# DataDriven_sheet4_sim_connectors.net
KiCad netlist of a schematic drawn in Altium Designer
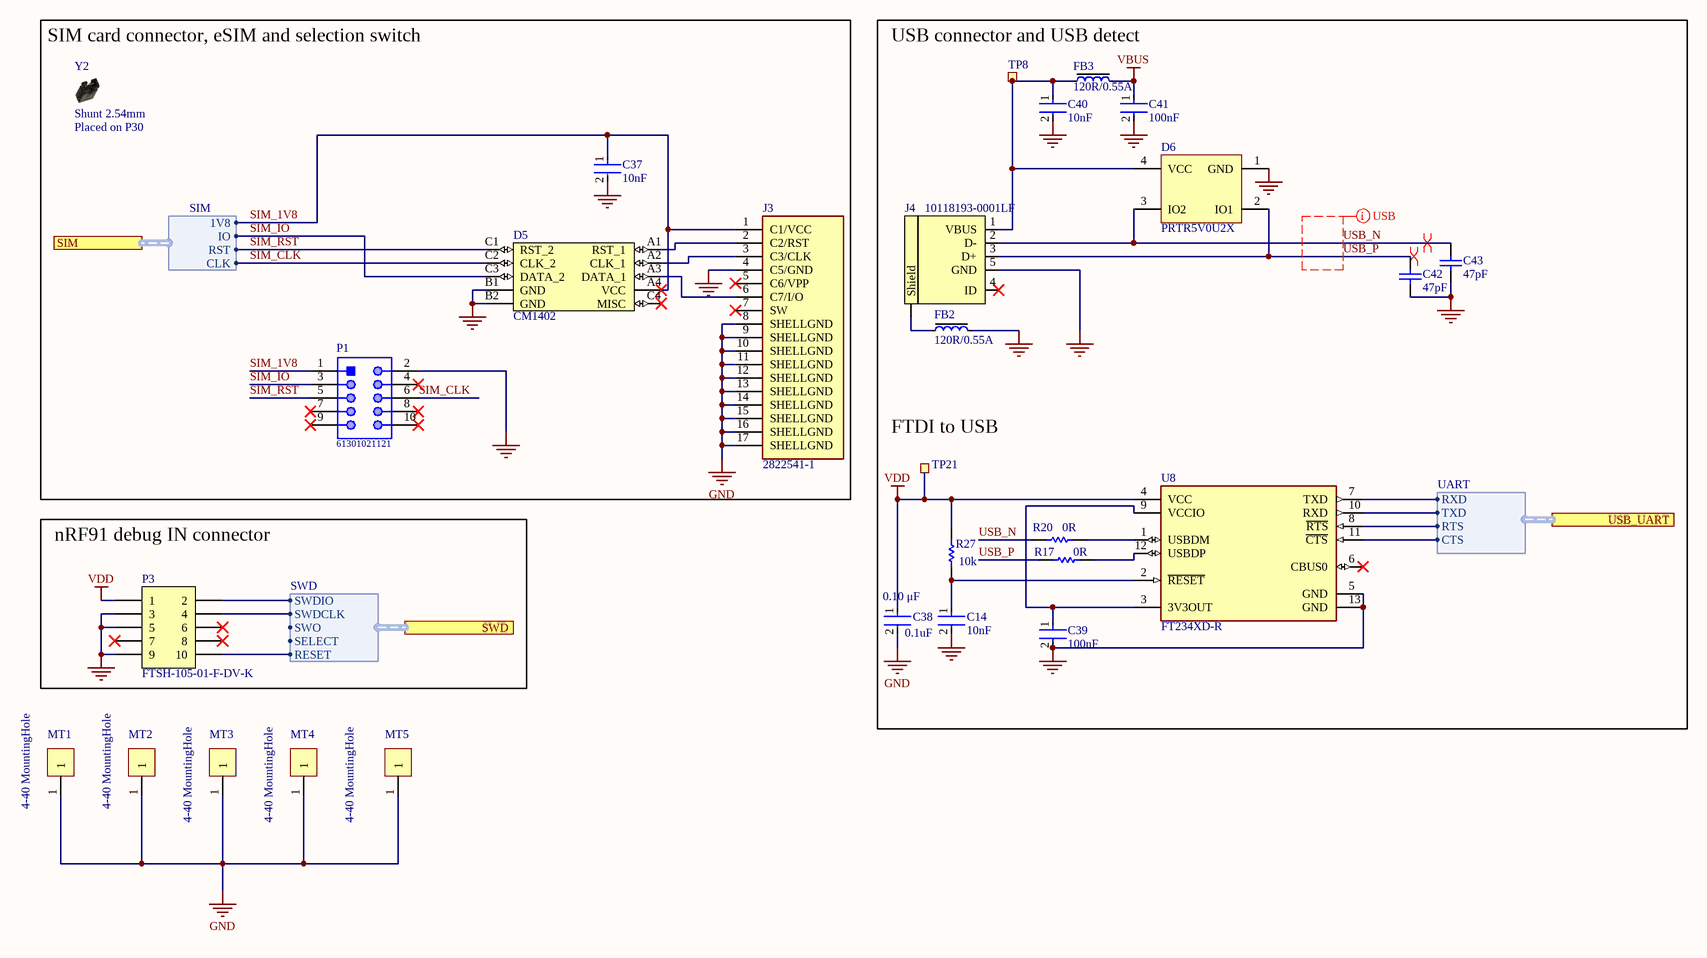
[diagram p0: DataDriven_sheet4_sim_connectors.SchDoc]

(export (version "E")
  (design (tool "Eeschema 10.0.6"))
  (components
    (comp (ref "C14")
      (value "10nF")
      (footprint "FP-CC0603-DA-MFG")
      (description "CAP CER 10000PF 50V X7R 0603")
      (fields (field (name "TOLERANCE") "0.1") (field (name "MANUFACTURER PART NUMBER") "CC0603KRX7R9BB103"))
      (libsource (lib "Altium Content Vault") (part "11868f565c42a9108669ba33697ecf6"))
    )
    (comp (ref "C37")
      (value "10nF")
      (footprint "FP-CC0603-DA-MFG")
      (description "CAP CER 10000PF 50V X7R 0603")
      (fields (field (name "TOLERANCE") "0.1") (field (name "MANUFACTURER PART NUMBER") "CC0603KRX7R9BB103"))
      (libsource (lib "Altium Content Vault") (part "11868f565c42a9108669ba33697ecf6"))
    )
    (comp (ref "C38")
      (value "0.1uF")
      (footprint "FP-C0603C-CF-MFG")
      (description "CAP CER 0.1UF 50V X7R 0603")
      (fields
        (field (name "TOLERANCE") "0.1")
        (field (name "MANUFACTURER") "KEMET")
        (field (name "CAPACITANCE") "0.10 μF")
      )
      (libsource (lib "Altium Content Vault") (part "b4654b650e69147ec39a6b967a45e02"))
    )
    (comp (ref "C39")
      (value "100nF")
      (footprint "FP-CGA3E-0_3-0_1-IPC_A")
      (description "Cap Ceramic 100nF 50V X7R 10% Pad SMD 0603 +125°C Automotive T/R")
      (fields (field (name "TOLERANCE") "10%") (field (name "VOLTAGE") "50V"))
      (libsource (lib "Altium Content Vault") (part "b4654b650e69147ec39a6b967a45e02"))
    )
    (comp (ref "C40")
      (value "10nF")
      (footprint "FP-CC0603-DA-MFG")
      (description "CAP CER 10000PF 50V X7R 0603")
      (fields (field (name "TOLERANCE") "0.1") (field (name "MANUFACTURER PART NUMBER") "CC0603KRX7R9BB103"))
      (libsource (lib "Altium Content Vault") (part "11868f565c42a9108669ba33697ecf6"))
    )
    (comp (ref "C41")
      (value "100nF")
      (footprint "FP-CGA3E-0_3-0_1-MFG")
      (description "Cap Ceramic 100nF 50V X7R 10% Pad SMD 0603 +125°C Automotive T/R")
      (fields (field (name "TOLERANCE") "10%") (field (name "VOLTAGE") "50V"))
      (libsource (lib "Altium Content Vault") (part "b4654b650e69147ec39a6b967a45e02"))
    )
    (comp (ref "C42")
      (value "47pF")
      (footprint "CAPC1608X90X35ML10T15")
      (description "47 pF ±5% 50V Ceramic Capacitor C0G, NP0 0603 (1608 Metric)")
      (fields (field (name "MANUFACTURER") "Murata") (field (name "PART NUMBER") "GRM1885C1H470JA01D"))
      (libsource (lib "Altium Content Vault") (part "CAP"))
    )
    (comp (ref "C43")
      (value "47pF")
      (footprint "CAPC1608X90X35ML10T15")
      (description "47 pF ±5% 50V Ceramic Capacitor C0G, NP0 0603 (1608 Metric)")
      (fields (field (name "MANUFACTURER") "Murata") (field (name "PART NUMBER") "GRM1885C1H470JA01D"))
      (libsource (lib "Altium Content Vault") (part "CAP"))
    )
    (comp (ref "D5")
      (value "CM1402")
      (footprint "pca10090:CM1402")
      (description "EMI Network Filter Arrays SIM CARD EMI FILTER WITH ESD PROTECTION")
      (fields
        (field (name "MANUFACTURER") "ON Semiconductor")
        (field (name "MANUFACTURER PART NUMBER") "CM1402-03CP")
        (field (name "AUTHOR") "rsk")
      )
      (libsource (lib "AltiumLib") (part "CM1402"))
    )
    (comp (ref "D6")
      (value "PRTR5V0U2X")
      (footprint "pca10090:SOT190P230X110-4L")
      (description "Ultra low capacitance double rail-to-rail ESD protection diode")
      (fields (field (name "MANUFACTURER") "NXP Semiconductors") (field (name "AUTHOR") "rsk"))
      (libsource (lib "AltiumLib") (part "PRTR5V0U2X"))
    )
    (comp (ref "FB2")
      (value "120R/0.55A")
      (footprint "pca10090:INDC1005X04L")
      (description "Ferrite Bead, 120 Ohm @ 100MHz, 500mA, 250 mOhm Max")
      (fields
        (field (name "PART NUMBER") "FB0402-120R@100M-500mA")
        (field (name "MANUFACTURER") "Murata")
        (field (name "AUTHOR") "rsk")
      )
      (libsource (lib "AltiumLib") (part "IND_F"))
    )
    (comp (ref "FB3")
      (value "120R/0.55A")
      (footprint "pca10090:INDC1005X04L")
      (description "Ferrite Bead, 120 Ohm @ 100MHz, 500mA, 250 mOhm Max")
      (fields
        (field (name "PART NUMBER") "FB0402-120R@100M-500mA")
        (field (name "MANUFACTURER") "Murata")
        (field (name "AUTHOR") "rsk")
      )
      (libsource (lib "AltiumLib") (part "IND_F"))
    )
    (comp (ref "J3")
      (value "2822541-1")
      (footprint "TE_2822541-1")
      (description "7 _6 + 1_ Position Card Connector Micro SIM Surface Mount, Right Angle Gold")
      (fields (field (name "MF") "TE Connectivity") (field (name "DIGI-KEY_PART_NUMBER") "A141365CT-ND"))
      (libsource (lib "DataDriven") (part "2822541-1"))
    )
    (comp (ref "J4")
      (value "10118193-0001LF")
      (footprint "pca10090:USB-Micro-B-RA-SMD-PiP")
      (description "USB - micro B USB 2.0 Receptacle Connector 5 Position Surface Mount, Right Angle; Through Hole")
      (fields (field (name "MANUFACTURER") "Amphenol ICC (FCI)") (field (name "AUTHOR") "rsk"))
      (libsource (lib "AltiumLib") (part "MiniUSB-AB-SMT"))
    )
    (comp (ref "MT1")
      (value "4-40 MountingHole")
      (footprint "4-40 Mounting Hole")
      (description "4-40 Mounting Hole")
      (libsource (lib "DataDriven") (part "4-40 MountingHole"))
    )
    (comp (ref "MT2")
      (value "4-40 MountingHole")
      (footprint "4-40 Mounting Hole")
      (description "4-40 Mounting Hole")
      (libsource (lib "DataDriven") (part "4-40 MountingHole"))
    )
    (comp (ref "MT3")
      (value "4-40 MountingHole")
      (footprint "4-40 Mounting Hole")
      (description "4-40 Mounting Hole")
      (libsource (lib "DataDriven") (part "4-40 MountingHole"))
    )
    (comp (ref "MT4")
      (value "4-40 MountingHole")
      (footprint "4-40 Mounting Hole")
      (description "4-40 Mounting Hole")
      (libsource (lib "DataDriven") (part "4-40 MountingHole"))
    )
    (comp (ref "MT5")
      (value "4-40 MountingHole")
      (footprint "4-40 Mounting Hole")
      (description "4-40 Mounting Hole")
      (libsource (lib "DataDriven") (part "4-40 MountingHole"))
    )
    (comp (ref "P1")
      (value "61301021121")
      (footprint "61301021121")
      (description "THT Vertical Pin Header WR-PHD, Pitch 2.54 mm, Dual Row, 10 pins")
      (fields (field (name "MANUFACTURER") "Wurth Elektronik") (field (name "PUBLISHER") "WurthElektronik"))
      (libsource (lib "Altium Content Vault") (part "WE-CN-2P-M-R10"))
    )
    (comp (ref "P3")
      (value "FTSH-105-01-F-DV-K")
      (footprint "pca10090:HDR_2x5-SMD-1.27mm-K")
      (description "Pin Header 2x5, 1.27mm (50mil), SMD, Keying Shroud")
      (fields
        (field (name "PART NUMBER") "Pin Header 2x5 SMD, 1.27mm, KS")
        (field (name "MANUFACTURER") "Samtec")
        (field (name "AUTHOR") "rsk")
      )
      (libsource (lib "AltiumLib") (part "CONN-2x5"))
    )
    (comp (ref "R17")
      (value "0R")
      (footprint "RESC1608X55X25ML10T15")
      (description "Chip Resistor, 0 Ohm, +/- 5%, 0.1 W, -55 to 155 degC, 0603 (1608 Metric), RoHS, Tape and Reel")
      (fields (field (name "TOLERANCE") "5%") (field (name "MANUFACTURER") "Yageo"))
      (libsource (lib "Altium Content Vault") (part "RES-2"))
    )
    (comp (ref "R20")
      (value "0R")
      (footprint "RESC1608X55X25ML10T15")
      (description "Chip Resistor, 0 Ohm, +/- 5%, 0.1 W, -55 to 155 degC, 0603 (1608 Metric), RoHS, Tape and Reel")
      (fields (field (name "TOLERANCE") "5%") (field (name "MANUFACTURER") "Yageo"))
      (libsource (lib "Altium Content Vault") (part "RES-2"))
    )
    (comp (ref "R27")
      (value "10k")
      (footprint "RESC1609X55X30LL15T15")
      (description "Chip Resistor, 10 KOhm, +/- 1%, 0.1 W, -55 to 155 degC, 0603 (1608 Metric), RoHS, Tape and Reel")
      (fields (field (name "TOLERANCE") "1%") (field (name "MANUFACTURER") "Panasonic"))
      (libsource (lib "Altium Content Vault") (part "RES-2"))
    )
    (comp (ref "TP8")
      (value "Ø1.5mm,SMD")
      (footprint "pca10090:TP_SMD_D1.5mm")
      (description "1.5mm circular SMD testpad")
      (fields
        (field (name "PART NUMBER") "TP_SMD_Ø1.5MM")
        (field (name "MANUFACTURER") "Nordic Semiconductor")
        (field (name "AUTHOR") "rsk")
      )
      (libsource (lib "AltiumLib") (part "TESTPAD"))
    )
    (comp (ref "TP21")
      (value "Ø1.5mm,SMD")
      (footprint "pca10090:TP_SMD_D1.5mm")
      (description "1.5mm circular SMD testpad")
      (fields
        (field (name "PART NUMBER") "TP_SMD_Ø1.5MM")
        (field (name "MANUFACTURER") "Nordic Semiconductor")
        (field (name "AUTHOR") "rsk")
      )
      (libsource (lib "AltiumLib") (part "TESTPAD"))
    )
    (comp (ref "U8")
      (value "FT234XD-R")
      (footprint "FP-DFN-12-MFG")
      (description "IC USB SERIAL BASIC UART 12DFN")
      (fields (field (name "MANUFACTURER") "FTDI"))
      (libsource (lib "Altium Content Vault") (part "4bef3367ed9f9051bcb84ab46edda1c"))
    )
    (comp (ref "Y2")
      (value "Shunt 2.54mm")
      (footprint "pca10090:Shunt_2.54mm_Horizontal")
      (description "Shunt Jumper 2.54mm Black")
      (fields
        (field (name "PART NUMBER") "SNT-100-RD-G")
        (field (name "ASSEMBLY") "Placed on P30")
        (field (name "MANUFACTURER") "Samtec")
        (field (name "AUTHOR") "rsk")
      )
      (libsource (lib "AltiumLib") (part "Shunt_Jumper_2.54"))
    )
  )
  (nets
    (net (code "4") (name "/CTS") (class "Default")
      (node (ref "U8") (pin "11") (pinfunction "~{CTS}_11") (pintype "input"))
    )
    (net (code "5") (name "/RESET") (class "Default")
      (node (ref "P3") (pin "10") (pinfunction "10_10") (pintype "passive"))
    )
    (net (code "6") (name "/RTS") (class "Default")
      (node (ref "U8") (pin "8") (pinfunction "~{RTS}_8") (pintype "input"))
    )
    (net (code "7") (name "/RXD") (class "Default")
      (node (ref "U8") (pin "7") (pinfunction "TXD_7") (pintype "output"))
    )
    (net (code "8") (name "/SIM_1V8") (class "Default")
      (node (ref "C37") (pin "1") (pinfunction "1_1") (pintype "passive"))
      (node (ref "D5") (pin "A4") (pinfunction "VCC_A4") (pintype "power_in"))
      (node (ref "J3") (pin "1") (pinfunction "C1/VCC_1") (pintype "passive"))
      (node (ref "P1") (pin "1") (pinfunction "1_1") (pintype "passive"))
    )
    (net (code "9") (name "/SIM_CLK") (class "Default")
      (node (ref "D5") (pin "C2") (pinfunction "CLK_2_C2") (pintype "bidirectional"))
      (node (ref "P1") (pin "6") (pinfunction "6_6") (pintype "passive"))
    )
    (net (code "10") (name "/SIM_IO") (class "Default")
      (node (ref "D5") (pin "C3") (pinfunction "DATA_2_C3") (pintype "bidirectional"))
      (node (ref "P1") (pin "3") (pinfunction "3_3") (pintype "passive"))
    )
    (net (code "11") (name "/SIM_RST") (class "Default")
      (node (ref "D5") (pin "C1") (pinfunction "RST_2_C1") (pintype "bidirectional"))
      (node (ref "P1") (pin "5") (pinfunction "5_5") (pintype "passive"))
    )
    (net (code "12") (name "/SWDCLK") (class "Default")
      (node (ref "P3") (pin "4") (pinfunction "4_4") (pintype "passive"))
    )
    (net (code "13") (name "/SWDIO") (class "Default")
      (node (ref "P3") (pin "2") (pinfunction "2_2") (pintype "passive"))
    )
    (net (code "14") (name "/TXD") (class "Default")
      (node (ref "U8") (pin "10") (pinfunction "RXD_10") (pintype "output"))
    )
    (net (code "15") (name "/USB_N") (class "Default")
      (node (ref "C43") (pin "2") (pinfunction "2_2") (pintype "passive"))
      (node (ref "D6") (pin "3") (pinfunction "IO2_3") (pintype "passive"))
      (node (ref "J4") (pin "2") (pinfunction "D-_2") (pintype "passive"))
      (node (ref "R20") (pin "1") (pinfunction "1_1") (pintype "passive"))
    )
    (net (code "16") (name "/USB_P") (class "Default")
      (node (ref "C42") (pin "2") (pinfunction "2_2") (pintype "passive"))
      (node (ref "D6") (pin "2") (pinfunction "IO1_2") (pintype "passive"))
      (node (ref "J4") (pin "3") (pinfunction "D+_3") (pintype "passive"))
      (node (ref "R17") (pin "1") (pinfunction "1_1") (pintype "passive"))
    )
    (net (code "20") (name "GND") (class "Default")
      (node (ref "C14") (pin "2") (pinfunction "2_2") (pintype "passive"))
      (node (ref "C37") (pin "2") (pinfunction "2_2") (pintype "passive"))
      (node (ref "C38") (pin "2") (pinfunction "2_2") (pintype "passive"))
      (node (ref "C39") (pin "2") (pinfunction "2_2") (pintype "passive"))
      (node (ref "C40") (pin "2") (pinfunction "2_2") (pintype "passive"))
      (node (ref "C41") (pin "2") (pinfunction "2_2") (pintype "passive"))
      (node (ref "C42") (pin "1") (pinfunction "1_1") (pintype "passive"))
      (node (ref "C43") (pin "1") (pinfunction "1_1") (pintype "passive"))
      (node (ref "D5") (pin "B1") (pinfunction "GND_B1") (pintype "power_in"))
      (node (ref "D5") (pin "B2") (pinfunction "GND_B2") (pintype "power_in"))
      (node (ref "D6") (pin "1") (pinfunction "GND_1") (pintype "passive"))
      (node (ref "FB2") (pin "2") (pinfunction "2_2") (pintype "passive"))
      (node (ref "J3") (pin "10") (pinfunction "SHELLGND_10") (pintype "passive"))
      (node (ref "J3") (pin "11") (pinfunction "SHELLGND_11") (pintype "passive"))
      (node (ref "J3") (pin "12") (pinfunction "SHELLGND_12") (pintype "passive"))
      (node (ref "J3") (pin "13") (pinfunction "SHELLGND_13") (pintype "passive"))
      (node (ref "J3") (pin "14") (pinfunction "SHELLGND_14") (pintype "passive"))
      (node (ref "J3") (pin "15") (pinfunction "SHELLGND_15") (pintype "passive"))
      (node (ref "J3") (pin "16") (pinfunction "SHELLGND_16") (pintype "passive"))
      (node (ref "J3") (pin "17") (pinfunction "SHELLGND_17") (pintype "passive"))
      (node (ref "J3") (pin "4") (pinfunction "C5/GND_4") (pintype "passive"))
      (node (ref "J3") (pin "8") (pinfunction "SHELLGND_8") (pintype "passive"))
      (node (ref "J3") (pin "9") (pinfunction "SHELLGND_9") (pintype "passive"))
      (node (ref "J4") (pin "5") (pinfunction "GND_5") (pintype "power_in"))
      (node (ref "MT1") (pin "1") (pinfunction "1_1") (pintype "passive"))
      (node (ref "MT2") (pin "1") (pinfunction "1_1") (pintype "passive"))
      (node (ref "MT3") (pin "1") (pinfunction "1_1") (pintype "passive"))
      (node (ref "MT4") (pin "1") (pinfunction "1_1") (pintype "passive"))
      (node (ref "MT5") (pin "1") (pinfunction "1_1") (pintype "passive"))
      (node (ref "P1") (pin "2") (pinfunction "2_2") (pintype "passive"))
      (node (ref "P3") (pin "3") (pinfunction "3_3") (pintype "passive"))
      (node (ref "P3") (pin "5") (pinfunction "5_5") (pintype "passive"))
      (node (ref "P3") (pin "9") (pinfunction "9_9") (pintype "passive"))
      (node (ref "U8") (pin "13") (pinfunction "GND_13") (pintype "power_in"))
      (node (ref "U8") (pin "5") (pinfunction "GND_5") (pintype "power_in"))
    )
    (net (code "21") (name "Net-(D5-CLK_1)") (class "Default")
      (node (ref "D5") (pin "A2") (pinfunction "CLK_1_A2") (pintype "bidirectional"))
      (node (ref "J3") (pin "3") (pinfunction "C3/CLK_3") (pintype "passive"))
    )
    (net (code "22") (name "Net-(D5-DATA_1)") (class "Default")
      (node (ref "D5") (pin "A3") (pinfunction "DATA_1_A3") (pintype "bidirectional"))
      (node (ref "J3") (pin "6") (pinfunction "C7/I/O_6") (pintype "passive"))
    )
    (net (code "23") (name "Net-(D5-RST_1)") (class "Default")
      (node (ref "D5") (pin "A1") (pinfunction "RST_1_A1") (pintype "bidirectional"))
      (node (ref "J3") (pin "2") (pinfunction "C2/RST_2") (pintype "passive"))
    )
    (net (code "24") (name "Net-(D6-VCC)") (class "Default")
      (node (ref "C40") (pin "1") (pinfunction "1_1") (pintype "passive"))
      (node (ref "D6") (pin "4") (pinfunction "VCC_4") (pintype "passive"))
      (node (ref "FB3") (pin "1") (pinfunction "1_1") (pintype "passive"))
      (node (ref "J4") (pin "1") (pinfunction "VBUS_1") (pintype "power_in"))
      (node (ref "TP8") (pin "1") (pinfunction "1_1") (pintype "passive"))
    )
    (net (code "25") (name "Net-(J4-Shield)") (class "Default")
      (node (ref "FB2") (pin "1") (pinfunction "1_1") (pintype "passive"))
      (node (ref "J4") (pin "6") (pinfunction "Shield_6") (pintype "power_in"))
    )
    (net (code "26") (name "Net-(U8-3V3OUT)") (class "Default")
      (node (ref "C39") (pin "1") (pinfunction "1_1") (pintype "passive"))
      (node (ref "U8") (pin "3") (pinfunction "3V3OUT_3") (pintype "power_in"))
      (node (ref "U8") (pin "9") (pinfunction "VCCIO_9") (pintype "power_in"))
    )
    (net (code "27") (name "Net-(U8-USBDM)") (class "Default")
      (node (ref "R20") (pin "2") (pinfunction "2_2") (pintype "passive"))
      (node (ref "U8") (pin "1") (pinfunction "USBDM_1") (pintype "bidirectional"))
    )
    (net (code "28") (name "Net-(U8-USBDP)") (class "Default")
      (node (ref "R17") (pin "2") (pinfunction "2_2") (pintype "passive"))
      (node (ref "U8") (pin "12") (pinfunction "USBDP_12") (pintype "bidirectional"))
    )
    (net (code "29") (name "Net-(U8-~{RESET})") (class "Default")
      (node (ref "C14") (pin "1") (pinfunction "1_1") (pintype "passive"))
      (node (ref "R27") (pin "2") (pinfunction "2_2") (pintype "passive"))
      (node (ref "U8") (pin "2") (pinfunction "~{RESET}_2") (pintype "input"))
    )
    (net (code "30") (name "VBUS") (class "Default")
      (node (ref "C41") (pin "1") (pinfunction "1_1") (pintype "passive"))
      (node (ref "FB3") (pin "2") (pinfunction "2_2") (pintype "passive"))
    )
    (net (code "31") (name "VDD") (class "Default")
      (node (ref "C38") (pin "1") (pinfunction "1_1") (pintype "passive"))
      (node (ref "P3") (pin "1") (pinfunction "1_1") (pintype "passive"))
      (node (ref "R27") (pin "1") (pinfunction "1_1") (pintype "passive"))
      (node (ref "TP21") (pin "1") (pinfunction "1_1") (pintype "passive"))
      (node (ref "U8") (pin "4") (pinfunction "VCC_4") (pintype "power_in"))
    )
    (net (code "32") (name "unconnected-(D5-MISC-PadC4)") (class "Default")
      (node (ref "D5") (pin "C4") (pinfunction "MISC_C4") (pintype "bidirectional+no_connect"))
    )
    (net (code "33") (name "unconnected-(J3-C6{slash}VPP-Pad5)") (class "Default")
      (node (ref "J3") (pin "5") (pinfunction "C6/VPP_5") (pintype "passive+no_connect"))
    )
    (net (code "34") (name "unconnected-(J3-SW-Pad7)") (class "Default")
      (node (ref "J3") (pin "7") (pinfunction "SW_7") (pintype "passive+no_connect"))
    )
    (net (code "35") (name "unconnected-(J4-ID-Pad4)") (class "Default")
      (node (ref "J4") (pin "4") (pinfunction "ID_4") (pintype "passive+no_connect"))
    )
    (net (code "36") (name "unconnected-(P1-Pad4)") (class "Default")
      (node (ref "P1") (pin "4") (pinfunction "4_4") (pintype "passive+no_connect"))
    )
    (net (code "37") (name "unconnected-(P1-Pad7)") (class "Default")
      (node (ref "P1") (pin "7") (pinfunction "7_7") (pintype "passive+no_connect"))
    )
    (net (code "38") (name "unconnected-(P1-Pad8)") (class "Default")
      (node (ref "P1") (pin "8") (pinfunction "8_8") (pintype "passive+no_connect"))
    )
    (net (code "39") (name "unconnected-(P1-Pad9)") (class "Default")
      (node (ref "P1") (pin "9") (pinfunction "9_9") (pintype "passive+no_connect"))
    )
    (net (code "40") (name "unconnected-(P1-Pad10)") (class "Default")
      (node (ref "P1") (pin "10") (pinfunction "10_10") (pintype "passive+no_connect"))
    )
    (net (code "41") (name "unconnected-(P3-Pad6)") (class "Default")
      (node (ref "P3") (pin "6") (pinfunction "6_6") (pintype "passive+no_connect"))
    )
    (net (code "42") (name "unconnected-(P3-Pad7)") (class "Default")
      (node (ref "P3") (pin "7") (pinfunction "7_7") (pintype "passive+no_connect"))
    )
    (net (code "43") (name "unconnected-(P3-Pad8)") (class "Default")
      (node (ref "P3") (pin "8") (pinfunction "8_8") (pintype "passive+no_connect"))
    )
    (net (code "44") (name "unconnected-(U8-CBUS0-Pad6)") (class "Default")
      (node (ref "U8") (pin "6") (pinfunction "CBUS0_6") (pintype "bidirectional+no_connect"))
    )
  )
)
